# bufferboard.net
KiCad netlist of a schematic drawn in EAGLE
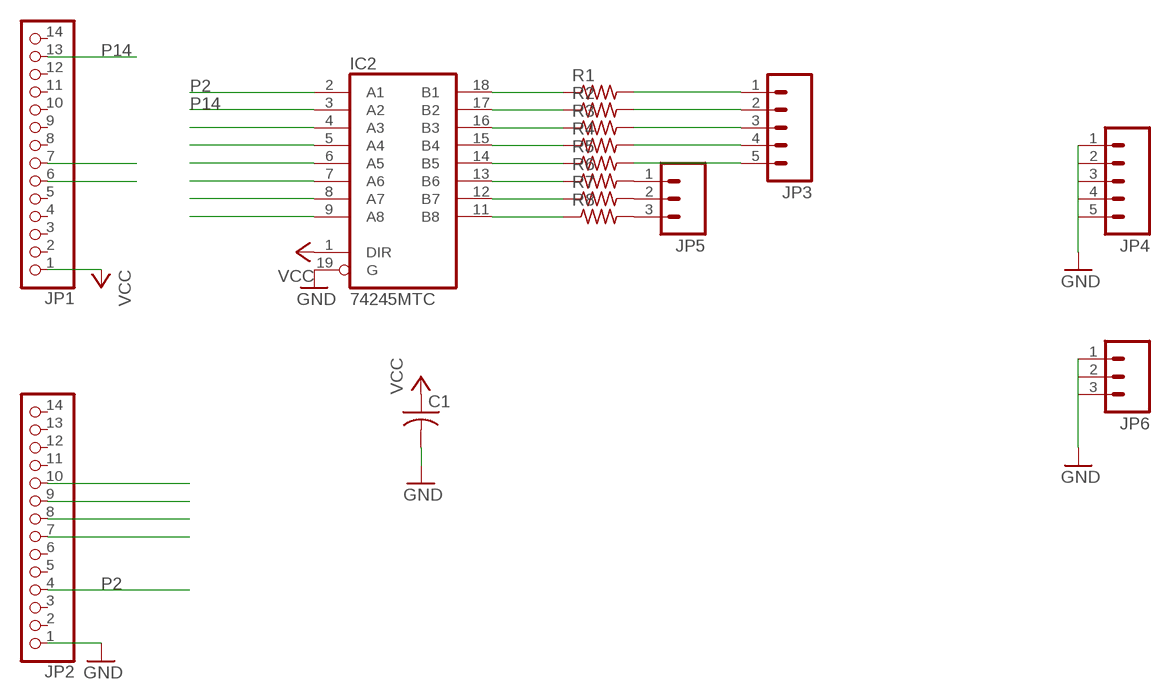
[diagram p0: schematic, sheet 1]

(export (version "E")
  (design (tool "Eeschema 10.0.6"))
  (components
    (comp (ref "C1")
      (value "C-USC0805")
      (footprint "eagle-import:C0805")
      (libsource (lib "eagle-import") (part "C-USC0805"))
    )
    (comp (ref "IC2")
      (value "74245MTC")
      (footprint "eagle-import:SSOP20")
      (libsource (lib "eagle-import") (part "74245MTC"))
    )
    (comp (ref "JP1")
      (value "PINHD-1X14-CB")
      (footprint "eagle-import:1X14-CB")
      (libsource (lib "eagle-import") (part "PINHD-1X14-CB"))
    )
    (comp (ref "JP2")
      (value "PINHD-1X14-CB")
      (footprint "eagle-import:1X14-CB")
      (libsource (lib "eagle-import") (part "PINHD-1X14-CB"))
    )
    (comp (ref "JP3")
      (value "M05NO_SILK")
      (footprint "eagle-import:1X05_NO_SILK")
      (libsource (lib "eagle-import") (part "M05NO_SILK"))
    )
    (comp (ref "JP4")
      (value "M05NO_SILK")
      (footprint "eagle-import:1X05_NO_SILK")
      (libsource (lib "eagle-import") (part "M05NO_SILK"))
    )
    (comp (ref "JP5")
      (value "M031X03_NO_SILK")
      (footprint "eagle-import:1X03_NO_SILK")
      (libsource (lib "eagle-import") (part "M031X03_NO_SILK"))
    )
    (comp (ref "JP6")
      (value "M031X03_NO_SILK")
      (footprint "eagle-import:1X03_NO_SILK")
      (libsource (lib "eagle-import") (part "M031X03_NO_SILK"))
    )
    (comp (ref "R1")
      (value "R-US_R0805")
      (footprint "eagle-import:R0805")
      (libsource (lib "eagle-import") (part "R-US_R0805"))
    )
    (comp (ref "R2")
      (value "R-US_R0805")
      (footprint "eagle-import:R0805")
      (libsource (lib "eagle-import") (part "R-US_R0805"))
    )
    (comp (ref "R3")
      (value "R-US_R0805")
      (footprint "eagle-import:R0805")
      (libsource (lib "eagle-import") (part "R-US_R0805"))
    )
    (comp (ref "R4")
      (value "R-US_R0805")
      (footprint "eagle-import:R0805")
      (libsource (lib "eagle-import") (part "R-US_R0805"))
    )
    (comp (ref "R5")
      (value "R-US_R0805")
      (footprint "eagle-import:R0805")
      (libsource (lib "eagle-import") (part "R-US_R0805"))
    )
    (comp (ref "R6")
      (value "R-US_R0805")
      (footprint "eagle-import:R0805")
      (libsource (lib "eagle-import") (part "R-US_R0805"))
    )
    (comp (ref "R7")
      (value "R-US_R0805")
      (footprint "eagle-import:R0805")
      (libsource (lib "eagle-import") (part "R-US_R0805"))
    )
    (comp (ref "R8")
      (value "R-US_R0805")
      (footprint "eagle-import:R0805")
      (libsource (lib "eagle-import") (part "R-US_R0805"))
    )
  )
  (nets
    (net (code "1") (name "/P2") (class "Default")
      (node (ref "IC2") (pin "2") (pinfunction "A1_2") (pintype "bidirectional"))
      (node (ref "JP2") (pin "4") (pinfunction "4_4") (pintype "passive"))
    )
    (net (code "2") (name "/P5") (class "Default")
      (node (ref "IC2") (pin "9") (pinfunction "A8_9") (pintype "bidirectional"))
      (node (ref "JP2") (pin "7") (pinfunction "7_7") (pintype "passive"))
    )
    (net (code "3") (name "/P6") (class "Default")
      (node (ref "IC2") (pin "6") (pinfunction "A5_6") (pintype "bidirectional"))
      (node (ref "JP2") (pin "8") (pinfunction "8_8") (pintype "passive"))
    )
    (net (code "4") (name "/P7") (class "Default")
      (node (ref "IC2") (pin "4") (pinfunction "A3_4") (pintype "bidirectional"))
      (node (ref "JP2") (pin "9") (pinfunction "9_9") (pintype "passive"))
    )
    (net (code "5") (name "/P8") (class "Default")
      (node (ref "IC2") (pin "5") (pinfunction "A4_5") (pintype "bidirectional"))
      (node (ref "JP2") (pin "10") (pinfunction "10_10") (pintype "passive"))
    )
    (net (code "6") (name "/P14") (class "Default")
      (node (ref "IC2") (pin "3") (pinfunction "A2_3") (pintype "bidirectional"))
      (node (ref "JP1") (pin "13") (pinfunction "13_13") (pintype "passive"))
    )
    (net (code "7") (name "/P20") (class "Default")
      (node (ref "IC2") (pin "7") (pinfunction "A6_7") (pintype "bidirectional"))
      (node (ref "JP1") (pin "7") (pinfunction "7_7") (pintype "passive"))
    )
    (net (code "8") (name "/P21") (class "Default")
      (node (ref "IC2") (pin "8") (pinfunction "A7_8") (pintype "bidirectional"))
      (node (ref "JP1") (pin "6") (pinfunction "6_6") (pintype "passive"))
    )
    (net (code "9") (name "GND") (class "Default")
      (node (ref "C1") (pin "2") (pinfunction "2_2") (pintype "passive"))
      (node (ref "IC2") (pin "19") (pinfunction "G_19") (pintype "input"))
      (node (ref "JP2") (pin "1") (pinfunction "1_1") (pintype "passive"))
      (node (ref "JP4") (pin "1") (pinfunction "1_1") (pintype "passive"))
      (node (ref "JP4") (pin "2") (pinfunction "2_2") (pintype "passive"))
      (node (ref "JP4") (pin "3") (pinfunction "3_3") (pintype "passive"))
      (node (ref "JP4") (pin "4") (pinfunction "4_4") (pintype "passive"))
      (node (ref "JP4") (pin "5") (pinfunction "5_5") (pintype "passive"))
      (node (ref "JP6") (pin "1") (pinfunction "1_1") (pintype "passive"))
      (node (ref "JP6") (pin "2") (pinfunction "2_2") (pintype "passive"))
      (node (ref "JP6") (pin "3") (pinfunction "3_3") (pintype "passive"))
    )
    (net (code "10") (name "Net-(IC2A-B1)") (class "Default")
      (node (ref "IC2") (pin "18") (pinfunction "B1_18") (pintype "bidirectional"))
      (node (ref "R1") (pin "1") (pinfunction "1_1") (pintype "passive"))
    )
    (net (code "11") (name "Net-(IC2A-B2)") (class "Default")
      (node (ref "IC2") (pin "17") (pinfunction "B2_17") (pintype "bidirectional"))
      (node (ref "R2") (pin "1") (pinfunction "1_1") (pintype "passive"))
    )
    (net (code "12") (name "Net-(IC2A-B3)") (class "Default")
      (node (ref "IC2") (pin "16") (pinfunction "B3_16") (pintype "bidirectional"))
      (node (ref "R3") (pin "1") (pinfunction "1_1") (pintype "passive"))
    )
    (net (code "13") (name "Net-(IC2A-B4)") (class "Default")
      (node (ref "IC2") (pin "15") (pinfunction "B4_15") (pintype "bidirectional"))
      (node (ref "R4") (pin "1") (pinfunction "1_1") (pintype "passive"))
    )
    (net (code "14") (name "Net-(IC2A-B5)") (class "Default")
      (node (ref "IC2") (pin "14") (pinfunction "B5_14") (pintype "bidirectional"))
      (node (ref "R5") (pin "1") (pinfunction "1_1") (pintype "passive"))
    )
    (net (code "15") (name "Net-(IC2A-B6)") (class "Default")
      (node (ref "IC2") (pin "13") (pinfunction "B6_13") (pintype "bidirectional"))
      (node (ref "R6") (pin "1") (pinfunction "1_1") (pintype "passive"))
    )
    (net (code "16") (name "Net-(IC2A-B7)") (class "Default")
      (node (ref "IC2") (pin "12") (pinfunction "B7_12") (pintype "bidirectional"))
      (node (ref "R7") (pin "1") (pinfunction "1_1") (pintype "passive"))
    )
    (net (code "17") (name "Net-(IC2A-B8)") (class "Default")
      (node (ref "IC2") (pin "11") (pinfunction "B8_11") (pintype "bidirectional"))
      (node (ref "R8") (pin "1") (pinfunction "1_1") (pintype "passive"))
    )
    (net (code "18") (name "Net-(JP3-Pad1)") (class "Default")
      (node (ref "JP3") (pin "1") (pinfunction "1_1") (pintype "passive"))
      (node (ref "R1") (pin "2") (pinfunction "2_2") (pintype "passive"))
    )
    (net (code "19") (name "Net-(JP3-Pad2)") (class "Default")
      (node (ref "JP3") (pin "2") (pinfunction "2_2") (pintype "passive"))
      (node (ref "R2") (pin "2") (pinfunction "2_2") (pintype "passive"))
    )
    (net (code "20") (name "Net-(JP3-Pad3)") (class "Default")
      (node (ref "JP3") (pin "3") (pinfunction "3_3") (pintype "passive"))
      (node (ref "R3") (pin "2") (pinfunction "2_2") (pintype "passive"))
    )
    (net (code "21") (name "Net-(JP3-Pad4)") (class "Default")
      (node (ref "JP3") (pin "4") (pinfunction "4_4") (pintype "passive"))
      (node (ref "R4") (pin "2") (pinfunction "2_2") (pintype "passive"))
    )
    (net (code "22") (name "Net-(JP3-Pad5)") (class "Default")
      (node (ref "JP3") (pin "5") (pinfunction "5_5") (pintype "passive"))
      (node (ref "R5") (pin "2") (pinfunction "2_2") (pintype "passive"))
    )
    (net (code "23") (name "Net-(JP5-Pad1)") (class "Default")
      (node (ref "JP5") (pin "1") (pinfunction "1_1") (pintype "passive"))
      (node (ref "R6") (pin "2") (pinfunction "2_2") (pintype "passive"))
    )
    (net (code "24") (name "Net-(JP5-Pad2)") (class "Default")
      (node (ref "JP5") (pin "2") (pinfunction "2_2") (pintype "passive"))
      (node (ref "R7") (pin "2") (pinfunction "2_2") (pintype "passive"))
    )
    (net (code "25") (name "Net-(JP5-Pad3)") (class "Default")
      (node (ref "JP5") (pin "3") (pinfunction "3_3") (pintype "passive"))
      (node (ref "R8") (pin "2") (pinfunction "2_2") (pintype "passive"))
    )
    (net (code "26") (name "VCC") (class "Default")
      (node (ref "C1") (pin "1") (pinfunction "1_1") (pintype "passive"))
      (node (ref "IC2") (pin "1") (pinfunction "DIR_1") (pintype "input"))
      (node (ref "JP1") (pin "1") (pinfunction "1_1") (pintype "passive"))
    )
    (net (code "27") (name "unconnected-(JP1-Pad2)") (class "Default")
      (node (ref "JP1") (pin "2") (pinfunction "2_2") (pintype "passive"))
    )
    (net (code "28") (name "unconnected-(JP1-Pad3)") (class "Default")
      (node (ref "JP1") (pin "3") (pinfunction "3_3") (pintype "passive"))
    )
    (net (code "29") (name "unconnected-(JP1-Pad4)") (class "Default")
      (node (ref "JP1") (pin "4") (pinfunction "4_4") (pintype "passive"))
    )
    (net (code "30") (name "unconnected-(JP1-Pad5)") (class "Default")
      (node (ref "JP1") (pin "5") (pinfunction "5_5") (pintype "passive"))
    )
    (net (code "31") (name "unconnected-(JP1-Pad8)") (class "Default")
      (node (ref "JP1") (pin "8") (pinfunction "8_8") (pintype "passive"))
    )
    (net (code "32") (name "unconnected-(JP1-Pad9)") (class "Default")
      (node (ref "JP1") (pin "9") (pinfunction "9_9") (pintype "passive"))
    )
    (net (code "33") (name "unconnected-(JP1-Pad10)") (class "Default")
      (node (ref "JP1") (pin "10") (pinfunction "10_10") (pintype "passive"))
    )
    (net (code "34") (name "unconnected-(JP1-Pad11)") (class "Default")
      (node (ref "JP1") (pin "11") (pinfunction "11_11") (pintype "passive"))
    )
    (net (code "35") (name "unconnected-(JP1-Pad12)") (class "Default")
      (node (ref "JP1") (pin "12") (pinfunction "12_12") (pintype "passive"))
    )
    (net (code "36") (name "unconnected-(JP1-Pad14)") (class "Default")
      (node (ref "JP1") (pin "14") (pinfunction "14_14") (pintype "passive"))
    )
    (net (code "37") (name "unconnected-(JP2-Pad2)") (class "Default")
      (node (ref "JP2") (pin "2") (pinfunction "2_2") (pintype "passive"))
    )
    (net (code "38") (name "unconnected-(JP2-Pad3)") (class "Default")
      (node (ref "JP2") (pin "3") (pinfunction "3_3") (pintype "passive"))
    )
    (net (code "39") (name "unconnected-(JP2-Pad5)") (class "Default")
      (node (ref "JP2") (pin "5") (pinfunction "5_5") (pintype "passive"))
    )
    (net (code "40") (name "unconnected-(JP2-Pad6)") (class "Default")
      (node (ref "JP2") (pin "6") (pinfunction "6_6") (pintype "passive"))
    )
    (net (code "41") (name "unconnected-(JP2-Pad11)") (class "Default")
      (node (ref "JP2") (pin "11") (pinfunction "11_11") (pintype "passive"))
    )
    (net (code "42") (name "unconnected-(JP2-Pad12)") (class "Default")
      (node (ref "JP2") (pin "12") (pinfunction "12_12") (pintype "passive"))
    )
    (net (code "43") (name "unconnected-(JP2-Pad13)") (class "Default")
      (node (ref "JP2") (pin "13") (pinfunction "13_13") (pintype "passive"))
    )
    (net (code "44") (name "unconnected-(JP2-Pad14)") (class "Default")
      (node (ref "JP2") (pin "14") (pinfunction "14_14") (pintype "passive"))
    )
  )
)
